# 411_Preliminary_Design__Group8_rev4_5.net
KiCad netlist of a schematic drawn in EAGLE
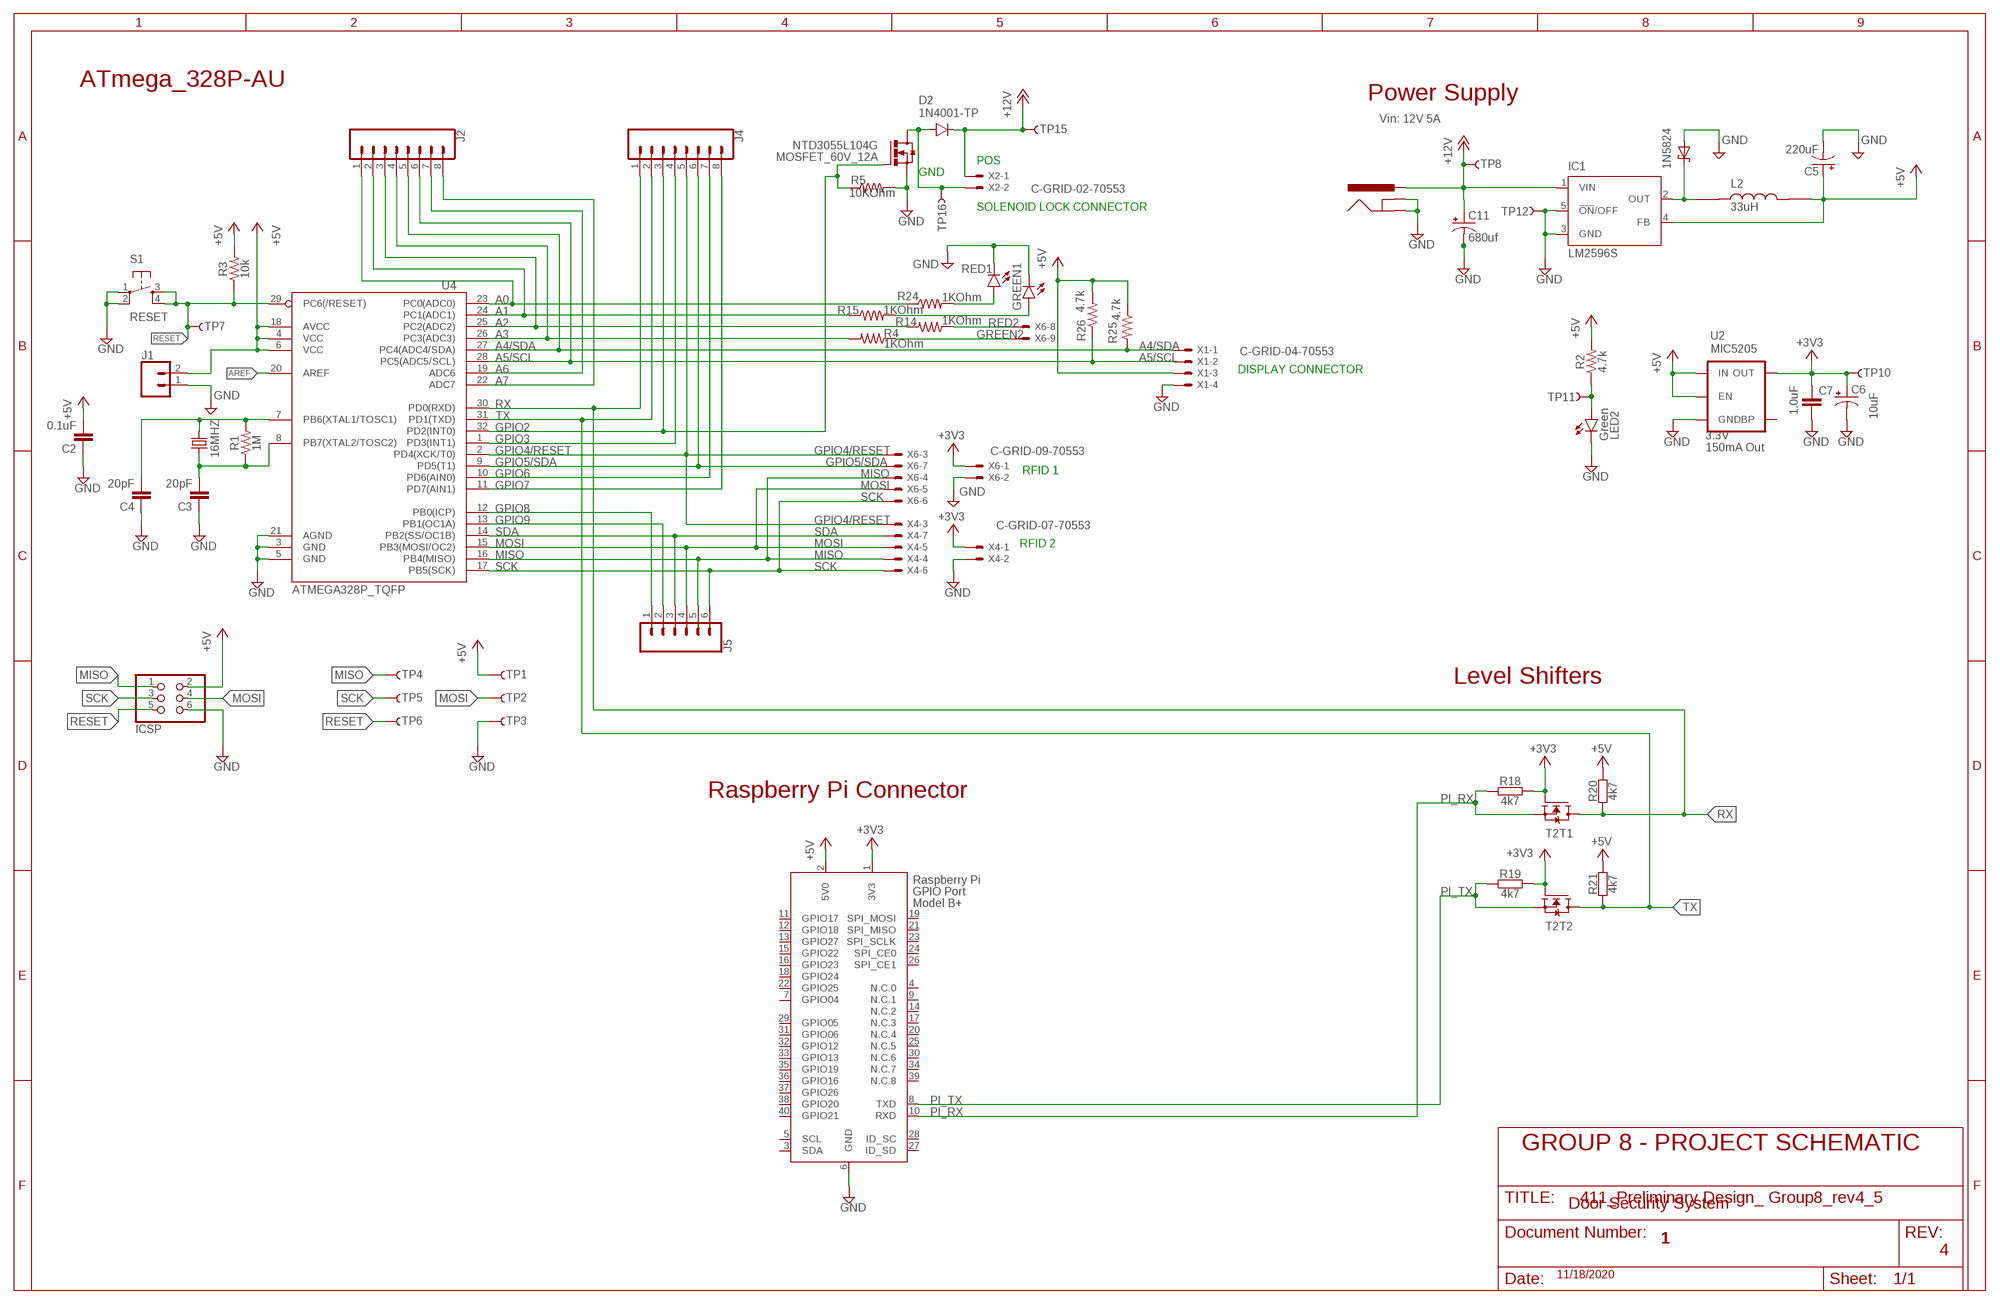
[diagram p0: schematic, sheet 1]

(export (version "E")
  (design (tool "Eeschema 10.0.6"))
  (components
    (comp (ref "1N5824")
      (value "SCHOTTKY-DIODECB429-15")
      (footprint "eagle-import:CB429-15")
      (libsource (lib "eagle-import") (part "SCHOTTKY-DIODECB429-15"))
    )
    (comp (ref "16MHZ")
      (value "16MHZ")
      (footprint "eagle-import:HC49_S")
      (libsource (lib "eagle-import") (part "CRYSTALHC49S"))
    )
    (comp (ref "C2")
      (value "0.1uF")
      (footprint "eagle-import:0603")
      (libsource (lib "eagle-import") (part "0.1UF-0603-25V-(+80/-20%)"))
    )
    (comp (ref "C3")
      (value "20pF")
      (footprint "eagle-import:0603")
      (libsource (lib "eagle-import") (part "0.1UF-0603-25V-(+80/-20%)"))
    )
    (comp (ref "C4")
      (value "20pF")
      (footprint "eagle-import:0603")
      (libsource (lib "eagle-import") (part "0.1UF-0603-25V-(+80/-20%)"))
    )
    (comp (ref "C5")
      (value "220uF")
      (footprint "eagle-import:153CLV-0605")
      (libsource (lib "eagle-import") (part "CPOL-US153CLV-0605"))
    )
    (comp (ref "C6")
      (value "10uF")
      (footprint "eagle-import:EIA3216")
      (libsource (lib "eagle-import") (part "10UF-POLAR-EIA3216-16V-10%(TANT)"))
    )
    (comp (ref "C7")
      (value "1.0uF")
      (footprint "eagle-import:0603")
      (libsource (lib "eagle-import") (part "1.0UF-0603-16V-10%"))
    )
    (comp (ref "C11")
      (value "680uf")
      (footprint "eagle-import:153CLV-0605")
      (libsource (lib "eagle-import") (part "CPOL-US153CLV-0605"))
    )
    (comp (ref "D2")
      (value "1N4001-TP")
      (footprint "eagle-import:DO41-10")
      (libsource (lib "eagle-import") (part "1N4004"))
    )
    (comp (ref "GREEN1")
      (value "LED5MM")
      (footprint "eagle-import:LED5MM")
      (libsource (lib "eagle-import") (part "led_259_LED5MM"))
    )
    (comp (ref "IC1")
      (value "LM2596S")
      (footprint "eagle-import:TO263-5")
      (fields (field (name "MF") "NATIONAL SEMICONDUCTOR") (field (name "MPN") "LM2596S-ADJ/NOPB"))
      (libsource (lib "eagle-import") (part "LM2596S"))
    )
    (comp (ref "ICSP")
      (value "ICSP")
      (footprint "eagle-import:2X03")
      (libsource (lib "eagle-import") (part "PINHD-2X3"))
    )
    (comp (ref "J1")
      (value "CONN_02")
      (footprint "eagle-import:1X02")
      (libsource (lib "eagle-import") (part "CONN_02"))
    )
    (comp (ref "J2")
      (value "CONN_08\"")
      (footprint "eagle-import:1X08")
      (libsource (lib "eagle-import") (part "CONN_08{dblquote}"))
    )
    (comp (ref "J3")
      (value "POWER_JACKSUPER_BOMB_DIGITY")
      (footprint "eagle-import:POWER_JACK_SMD_OVERPASTE_SUPER_BOMB_DIGITY")
      (libsource (lib "eagle-import") (part "POWER_JACKSUPER_BOMB_DIGITY"))
    )
    (comp (ref "J4")
      (value "CONN_08\"")
      (footprint "eagle-import:1X08")
      (libsource (lib "eagle-import") (part "CONN_08{dblquote}"))
    )
    (comp (ref "J5")
      (value "CONN_06SILK_FEMALE_PTH")
      (footprint "eagle-import:1X06")
      (libsource (lib "eagle-import") (part "CONN_06SILK_FEMALE_PTH"))
    )
    (comp (ref "L2")
      (value "33uH")
      (footprint "eagle-import:IND_#B953AS-330M=P3")
      (fields
        (field (name "DIGI-KEY_PART_NUMBER") "490-14099-1-ND")
        (field (name "MF") "Murata")
        (field (name "MP") "#B953AS-330M=P3")
      )
      (libsource (lib "eagle-import") (part "#B953AS-330M=P3"))
    )
    (comp (ref "LED2")
      (value "Green")
      (footprint "eagle-import:LED-1206")
      (libsource (lib "eagle-import") (part "LED1206"))
    )
    (comp (ref "MOSFET_60V_12A")
      (value "NTD3055L104G")
      (footprint "eagle-import:DPAK3")
      (fields (field (name "MANUFACTURER") "ON SEMICONDUCTORS") (field (name "CREATED_BY") "PCBLayout.com"))
      (libsource (lib "eagle-import") (part "NTD3055L104G"))
    )
    (comp (ref "R1")
      (value "1M")
      (footprint "eagle-import:0603")
      (libsource (lib "eagle-import") (part "10KOHM-0603-1/10W-1%"))
    )
    (comp (ref "R2")
      (value "4.7k")
      (footprint "eagle-import:0603")
      (libsource (lib "eagle-import") (part "4.7KOHM-0603-1/10W-1%"))
    )
    (comp (ref "R3")
      (value "10k")
      (footprint "eagle-import:0603")
      (libsource (lib "eagle-import") (part "10KOHM-0603-1/10W-1%"))
    )
    (comp (ref "R4")
      (value "1KOhm")
      (footprint "eagle-import:M1406")
      (libsource (lib "eagle-import") (part "R-US_M1406"))
    )
    (comp (ref "R5")
      (value "10KOhm")
      (footprint "eagle-import:M1406")
      (libsource (lib "eagle-import") (part "R-US_M1406"))
    )
    (comp (ref "R14")
      (value "1KOhm")
      (footprint "eagle-import:M1406")
      (libsource (lib "eagle-import") (part "R-US_M1406"))
    )
    (comp (ref "R15")
      (value "1KOhm")
      (footprint "eagle-import:M1406")
      (libsource (lib "eagle-import") (part "R-US_M1406"))
    )
    (comp (ref "R18")
      (value "4k7")
      (footprint "eagle-import:C0402")
      (libsource (lib "eagle-import") (part "RESISTOR-0402"))
    )
    (comp (ref "R19")
      (value "4k7")
      (footprint "eagle-import:C0402")
      (libsource (lib "eagle-import") (part "RESISTOR-0402"))
    )
    (comp (ref "R20")
      (value "4k7")
      (footprint "eagle-import:C0402")
      (libsource (lib "eagle-import") (part "RESISTOR-0402"))
    )
    (comp (ref "R21")
      (value "4k7")
      (footprint "eagle-import:C0402")
      (libsource (lib "eagle-import") (part "RESISTOR-0402"))
    )
    (comp (ref "R24")
      (value "1KOhm")
      (footprint "eagle-import:M1406")
      (libsource (lib "eagle-import") (part "R-US_M1406"))
    )
    (comp (ref "R25")
      (value "4.7k")
      (footprint "eagle-import:0603")
      (libsource (lib "eagle-import") (part "4.7KOHM-0603-1/10W-1%"))
    )
    (comp (ref "R26")
      (value "4.7k")
      (footprint "eagle-import:0603")
      (libsource (lib "eagle-import") (part "4.7KOHM-0603-1/10W-1%"))
    )
    (comp (ref "RED1")
      (value "LED5MM")
      (footprint "eagle-import:LED5MM")
      (fields (field (name "SPICEPREFIX") "L"))
      (libsource (lib "eagle-import") (part "led_259_LED5MM"))
    )
    (comp (ref "S1")
      (value "RESET")
      (footprint "eagle-import:TACTILE-SWITCH-SMD")
      (libsource (lib "eagle-import") (part "SWITCH_SPST_4_PINSQUARE"))
    )
    (comp (ref "T2")
      (value "BSS138PS")
      (footprint "eagle-import:SOT363")
      (libsource (lib "eagle-import") (part "BSS138PS"))
    )
    (comp (ref "TP1")
      (value "TP-3x5")
      (footprint "eagle-import:PAD.03X.05")
      (libsource (lib "eagle-import") (part "TEST-POINT3X5"))
    )
    (comp (ref "TP2")
      (value "TP-3x5")
      (footprint "eagle-import:PAD.03X.05")
      (libsource (lib "eagle-import") (part "TEST-POINT3X5"))
    )
    (comp (ref "TP3")
      (value "TP-3x5")
      (footprint "eagle-import:PAD.03X.05")
      (libsource (lib "eagle-import") (part "TEST-POINT3X5"))
    )
    (comp (ref "TP4")
      (value "TP-3x5")
      (footprint "eagle-import:PAD.03X.05")
      (libsource (lib "eagle-import") (part "TEST-POINT3X5"))
    )
    (comp (ref "TP5")
      (value "TP-3x5")
      (footprint "eagle-import:PAD.03X.05")
      (libsource (lib "eagle-import") (part "SparkFun-Passives_TEST-POINT3X5"))
    )
    (comp (ref "TP6")
      (value "TP-3x5")
      (footprint "eagle-import:PAD.03X.05")
      (libsource (lib "eagle-import") (part "TEST-POINT3X5"))
    )
    (comp (ref "TP7")
      (value "TP-3x5")
      (footprint "eagle-import:PAD.03X.05")
      (libsource (lib "eagle-import") (part "TEST-POINT3X5"))
    )
    (comp (ref "TP8")
      (value "TP-3x5")
      (footprint "eagle-import:PAD.03X.05")
      (libsource (lib "eagle-import") (part "TEST-POINT3X5"))
    )
    (comp (ref "TP10")
      (value "TP-3x5")
      (footprint "eagle-import:PAD.03X.05")
      (libsource (lib "eagle-import") (part "TEST-POINT3X5"))
    )
    (comp (ref "TP11")
      (value "TP-3x5")
      (footprint "eagle-import:PAD.03X.05")
      (libsource (lib "eagle-import") (part "TEST-POINT3X5"))
    )
    (comp (ref "TP12")
      (value "TP-3x5")
      (footprint "eagle-import:PAD.03X.05")
      (libsource (lib "eagle-import") (part "TEST-POINT3X5"))
    )
    (comp (ref "TP15")
      (value "TP-3x5")
      (footprint "eagle-import:PAD.03X.05")
      (libsource (lib "eagle-import") (part "TEST-POINT3X5"))
    )
    (comp (ref "TP16")
      (value "TP-3x5")
      (footprint "eagle-import:PAD.03X.05")
      (libsource (lib "eagle-import") (part "TEST-POINT3X5"))
    )
    (comp (ref "U2")
      (value "MIC5205")
      (footprint "eagle-import:SOT23-5")
      (libsource (lib "eagle-import") (part "MIC52053.3V"))
    )
    (comp (ref "U4")
      (value "ATMEGA328P_TQFP")
      (footprint "eagle-import:TQFP32-08")
      (libsource (lib "eagle-import") (part "ATMEGA328P_TQFP"))
    )
    (comp (ref "X1")
      (value "C-GRID-04-70553")
      (footprint "eagle-import:70553-04")
      (fields (field (name "MF") "MOLEX"))
      (libsource (lib "eagle-import") (part "C-GRID-04-70553"))
    )
    (comp (ref "X2")
      (value "C-GRID-02-70553")
      (footprint "eagle-import:70553-02")
      (fields (field (name "MF") "MOLEX"))
      (libsource (lib "eagle-import") (part "C-GRID-02-70553"))
    )
    (comp (ref "X4")
      (value "C-GRID-07-70553")
      (footprint "eagle-import:70553-07")
      (fields (field (name "MF") "MOLEX"))
      (libsource (lib "eagle-import") (part "C-GRID-07-70553"))
    )
    (comp (ref "X5")
      (value "RASPI_BOARD_B+_E4P")
      (footprint "eagle-import:RASPI_BOARD_B+_EDGES_4DRILL_PAD")
      (libsource (lib "eagle-import") (part "RASPI_BOARD_B+_E4P"))
    )
    (comp (ref "X6")
      (value "C-GRID-09-70553")
      (footprint "eagle-import:70553-09")
      (fields (field (name "MF") "MOLEX"))
      (libsource (lib "eagle-import") (part "C-GRID-09-70553"))
    )
  )
  (nets
    (net (code "1") (name "+3V3") (class "Default")
      (node (ref "C6") (pin "+") (pinfunction "+_+") (pintype "passive"))
      (node (ref "C7") (pin "1") (pinfunction "1_1") (pintype "passive"))
      (node (ref "R18") (pin "2") (pinfunction "2_2") (pintype "passive"))
      (node (ref "R19") (pin "2") (pinfunction "2_2") (pintype "passive"))
      (node (ref "T2") (pin "2") (pinfunction "G_2") (pintype "passive"))
      (node (ref "T2") (pin "5") (pinfunction "G_5") (pintype "passive"))
      (node (ref "TP10") (pin "P$1") (pinfunction "1_P$1") (pintype "bidirectional"))
      (node (ref "U2") (pin "5") (pinfunction "OUT_5") (pintype "passive"))
      (node (ref "X4") (pin "1") (pinfunction "S_1") (pintype "passive"))
      (node (ref "X5") (pin "1") (pinfunction "3V3_1") (pintype "power_in"))
      (node (ref "X6") (pin "1") (pinfunction "S_1") (pintype "passive"))
    )
    (net (code "2") (name "+5V") (class "Default")
      (node (ref "C2") (pin "2") (pinfunction "2_2") (pintype "passive"))
      (node (ref "C5") (pin "+") (pinfunction "+_+") (pintype "passive"))
      (node (ref "IC1") (pin "4") (pinfunction "FB_4") (pintype "input"))
      (node (ref "ICSP") (pin "2") (pinfunction "2_2") (pintype "passive"))
      (node (ref "J1") (pin "2") (pinfunction "2_2") (pintype "passive"))
      (node (ref "L2") (pin "2") (pinfunction "2_2") (pintype "passive"))
      (node (ref "R2") (pin "2") (pinfunction "2_2") (pintype "passive"))
      (node (ref "R20") (pin "2") (pinfunction "2_2") (pintype "passive"))
      (node (ref "R21") (pin "2") (pinfunction "2_2") (pintype "passive"))
      (node (ref "R25") (pin "1") (pinfunction "1_1") (pintype "passive"))
      (node (ref "R26") (pin "2") (pinfunction "2_2") (pintype "passive"))
      (node (ref "R3") (pin "2") (pinfunction "2_2") (pintype "passive"))
      (node (ref "TP1") (pin "P$1") (pinfunction "1_P$1") (pintype "bidirectional"))
      (node (ref "U2") (pin "1") (pinfunction "IN_1") (pintype "input"))
      (node (ref "U2") (pin "3") (pinfunction "EN_3") (pintype "input"))
      (node (ref "U4") (pin "18") (pinfunction "AVCC_18") (pintype "bidirectional"))
      (node (ref "U4") (pin "4") (pinfunction "VCC_4") (pintype "bidirectional"))
      (node (ref "U4") (pin "6") (pinfunction "VCC_6") (pintype "bidirectional"))
      (node (ref "X1") (pin "3") (pinfunction "S_3") (pintype "passive"))
      (node (ref "X5") (pin "2") (pinfunction "5V0_2") (pintype "power_in"))
    )
    (net (code "3") (name "+12V") (class "Default")
      (node (ref "C11") (pin "+") (pinfunction "+_+") (pintype "passive"))
      (node (ref "D2") (pin "C") (pinfunction "C_C") (pintype "passive"))
      (node (ref "IC1") (pin "1") (pinfunction "VIN_1") (pintype "input"))
      (node (ref "J3") (pin "VIN0") (pinfunction "PWR_VIN0") (pintype "bidirectional"))
      (node (ref "TP15") (pin "P$1") (pinfunction "1_P$1") (pintype "bidirectional"))
      (node (ref "TP8") (pin "P$1") (pinfunction "1_P$1") (pintype "bidirectional"))
      (node (ref "X2") (pin "1") (pinfunction "S_1") (pintype "passive"))
    )
    (net (code "4") (name "/A0") (class "Default")
      (node (ref "J2") (pin "1") (pinfunction "1_1") (pintype "passive"))
      (node (ref "R24") (pin "1") (pinfunction "1_1") (pintype "passive"))
      (node (ref "U4") (pin "23") (pinfunction "PC0(ADC0)_23") (pintype "bidirectional"))
    )
    (net (code "5") (name "/A1") (class "Default")
      (node (ref "J2") (pin "2") (pinfunction "2_2") (pintype "passive"))
      (node (ref "R15") (pin "1") (pinfunction "1_1") (pintype "passive"))
      (node (ref "U4") (pin "24") (pinfunction "PC1(ADC1)_24") (pintype "bidirectional"))
    )
    (net (code "6") (name "/A2") (class "Default")
      (node (ref "J2") (pin "3") (pinfunction "3_3") (pintype "passive"))
      (node (ref "R14") (pin "2") (pinfunction "2_2") (pintype "passive"))
      (node (ref "U4") (pin "25") (pinfunction "PC2(ADC2)_25") (pintype "bidirectional"))
    )
    (net (code "7") (name "/A3") (class "Default")
      (node (ref "J2") (pin "4") (pinfunction "4_4") (pintype "passive"))
      (node (ref "R4") (pin "2") (pinfunction "2_2") (pintype "passive"))
      (node (ref "U4") (pin "26") (pinfunction "PC3(ADC3)_26") (pintype "bidirectional"))
    )
    (net (code "8") (name "/A4{slash}SDA") (class "Default")
      (node (ref "J2") (pin "5") (pinfunction "5_5") (pintype "passive"))
      (node (ref "R25") (pin "2") (pinfunction "2_2") (pintype "passive"))
      (node (ref "U4") (pin "27") (pinfunction "PC4(ADC4/SDA)_27") (pintype "bidirectional"))
      (node (ref "X1") (pin "1") (pinfunction "S_1") (pintype "passive"))
    )
    (net (code "9") (name "/A5{slash}SCL") (class "Default")
      (node (ref "J2") (pin "6") (pinfunction "6_6") (pintype "passive"))
      (node (ref "R26") (pin "1") (pinfunction "1_1") (pintype "passive"))
      (node (ref "U4") (pin "28") (pinfunction "PC5(ADC5/SCL)_28") (pintype "bidirectional"))
      (node (ref "X1") (pin "2") (pinfunction "S_2") (pintype "passive"))
    )
    (net (code "10") (name "/A6") (class "Default")
      (node (ref "J2") (pin "7") (pinfunction "7_7") (pintype "passive"))
      (node (ref "U4") (pin "19") (pinfunction "ADC6_19") (pintype "bidirectional"))
    )
    (net (code "11") (name "/A7") (class "Default")
      (node (ref "J2") (pin "8") (pinfunction "8_8") (pintype "passive"))
      (node (ref "U4") (pin "22") (pinfunction "ADC7_22") (pintype "bidirectional"))
    )
    (net (code "12") (name "/GPIO2") (class "Default")
      (node (ref "J4") (pin "3") (pinfunction "3_3") (pintype "passive"))
      (node (ref "MOSFET_60V_12A") (pin "1") (pinfunction "G_1") (pintype "passive"))
      (node (ref "R5") (pin "1") (pinfunction "1_1") (pintype "passive"))
      (node (ref "U4") (pin "32") (pinfunction "PD2(INT0)_32") (pintype "bidirectional"))
    )
    (net (code "13") (name "/GPIO3") (class "Default")
      (node (ref "J4") (pin "4") (pinfunction "4_4") (pintype "passive"))
      (node (ref "U4") (pin "1") (pinfunction "PD3(INT1)_1") (pintype "bidirectional"))
    )
    (net (code "14") (name "/GPIO4{slash}RESET") (class "Default")
      (node (ref "J4") (pin "5") (pinfunction "5_5") (pintype "passive"))
      (node (ref "U4") (pin "2") (pinfunction "PD4(XCK/T0)_2") (pintype "bidirectional"))
      (node (ref "X4") (pin "3") (pinfunction "S_3") (pintype "passive"))
      (node (ref "X6") (pin "3") (pinfunction "S_3") (pintype "passive"))
    )
    (net (code "15") (name "/GPIO5{slash}SDA") (class "Default")
      (node (ref "J4") (pin "6") (pinfunction "6_6") (pintype "passive"))
      (node (ref "U4") (pin "9") (pinfunction "PD5(T1)_9") (pintype "bidirectional"))
      (node (ref "X6") (pin "7") (pinfunction "S_7") (pintype "passive"))
    )
    (net (code "16") (name "/GPIO6") (class "Default")
      (node (ref "J4") (pin "7") (pinfunction "7_7") (pintype "passive"))
      (node (ref "U4") (pin "10") (pinfunction "PD6(AIN0)_10") (pintype "bidirectional"))
    )
    (net (code "17") (name "/GPIO7") (class "Default")
      (node (ref "J4") (pin "8") (pinfunction "8_8") (pintype "passive"))
      (node (ref "U4") (pin "11") (pinfunction "PD7(AIN1)_11") (pintype "bidirectional"))
    )
    (net (code "18") (name "/GPIO8") (class "Default")
      (node (ref "J5") (pin "1") (pinfunction "1_1") (pintype "passive"))
      (node (ref "U4") (pin "12") (pinfunction "PB0(ICP)_12") (pintype "bidirectional"))
    )
    (net (code "19") (name "/GPIO9") (class "Default")
      (node (ref "J5") (pin "2") (pinfunction "2_2") (pintype "passive"))
      (node (ref "U4") (pin "13") (pinfunction "PB1(OC1A)_13") (pintype "bidirectional"))
    )
    (net (code "20") (name "/GREEN2") (class "Default")
      (node (ref "R4") (pin "1") (pinfunction "1_1") (pintype "passive"))
      (node (ref "X6") (pin "9") (pinfunction "S_9") (pintype "passive"))
    )
    (net (code "21") (name "/PI_RX") (class "Default")
      (node (ref "R18") (pin "1") (pinfunction "1_1") (pintype "passive"))
      (node (ref "T2") (pin "1") (pinfunction "S_1") (pintype "passive"))
      (node (ref "X5") (pin "10") (pinfunction "RXD_10") (pintype "bidirectional"))
    )
    (net (code "22") (name "/PI_TX") (class "Default")
      (node (ref "R19") (pin "1") (pinfunction "1_1") (pintype "passive"))
      (node (ref "T2") (pin "4") (pinfunction "S_4") (pintype "passive"))
      (node (ref "X5") (pin "8") (pinfunction "TXD_8") (pintype "bidirectional"))
    )
    (net (code "23") (name "/RED2") (class "Default")
      (node (ref "R14") (pin "1") (pinfunction "1_1") (pintype "passive"))
      (node (ref "X6") (pin "8") (pinfunction "S_8") (pintype "passive"))
    )
    (net (code "24") (name "/SDA") (class "Default")
      (node (ref "J5") (pin "3") (pinfunction "3_3") (pintype "passive"))
      (node (ref "U4") (pin "14") (pinfunction "PB2(SS/OC1B)_14") (pintype "bidirectional"))
      (node (ref "X4") (pin "7") (pinfunction "S_7") (pintype "passive"))
    )
    (net (code "25") (name "AREF") (class "Default")
      (node (ref "U4") (pin "20") (pinfunction "AREF_20") (pintype "bidirectional"))
    )
    (net (code "26") (name "GND") (class "Default")
      (node (ref "1N5824") (pin "A") (pinfunction "A_A") (pintype "passive"))
      (node (ref "C11") (pin "-") (pinfunction "-_-") (pintype "passive"))
      (node (ref "C2") (pin "1") (pinfunction "1_1") (pintype "passive"))
      (node (ref "C3") (pin "1") (pinfunction "1_1") (pintype "passive"))
      (node (ref "C4") (pin "1") (pinfunction "1_1") (pintype "passive"))
      (node (ref "C5") (pin "-") (pinfunction "-_-") (pintype "passive"))
      (node (ref "C6") (pin "-") (pinfunction "-_-") (pintype "passive"))
      (node (ref "C7") (pin "2") (pinfunction "2_2") (pintype "passive"))
      (node (ref "GREEN1") (pin "K") (pinfunction "C_K") (pintype "passive"))
      (node (ref "IC1") (pin "3") (pinfunction "GND_3") (pintype "power_in"))
      (node (ref "IC1") (pin "5") (pinfunction "~{ON}/OFF_5") (pintype "input"))
      (node (ref "ICSP") (pin "6") (pinfunction "6_6") (pintype "passive"))
      (node (ref "J1") (pin "1") (pinfunction "1_1") (pintype "passive"))
      (node (ref "J3") (pin "GND") (pinfunction "GNDBREAK_GND") (pintype "bidirectional"))
      (node (ref "J3") (pin "P$4") (pinfunction "GND_P$4") (pintype "bidirectional"))
      (node (ref "LED2") (pin "C") (pinfunction "C_C") (pintype "passive"))
      (node (ref "MOSFET_60V_12A") (pin "2") (pinfunction "S_2") (pintype "passive"))
      (node (ref "R5") (pin "2") (pinfunction "2_2") (pintype "passive"))
      (node (ref "RED1") (pin "K") (pinfunction "C_K") (pintype "passive"))
      (node (ref "S1") (pin "1") (pinfunction "1_1") (pintype "passive"))
      (node (ref "S1") (pin "2") (pinfunction "2_2") (pintype "passive"))
      (node (ref "TP12") (pin "P$1") (pinfunction "1_P$1") (pintype "bidirectional"))
      (node (ref "TP3") (pin "P$1") (pinfunction "1_P$1") (pintype "bidirectional"))
      (node (ref "U2") (pin "2") (pinfunction "GND_2") (pintype "input"))
      (node (ref "U4") (pin "21") (pinfunction "AGND_21") (pintype "bidirectional"))
      (node (ref "U4") (pin "3") (pinfunction "GND_3") (pintype "bidirectional"))
      (node (ref "U4") (pin "5") (pinfunction "GND_5") (pintype "bidirectional"))
      (node (ref "X1") (pin "4") (pinfunction "S_4") (pintype "passive"))
      (node (ref "X4") (pin "2") (pinfunction "S_2") (pintype "passive"))
      (node (ref "X5") (pin "6") (pinfunction "GND_6") (pintype "power_in"))
      (node (ref "X6") (pin "2") (pinfunction "S_2") (pintype "passive"))
    )
    (net (code "27") (name "MISO") (class "Default")
      (node (ref "ICSP") (pin "1") (pinfunction "1_1") (pintype "passive"))
      (node (ref "J5") (pin "5") (pinfunction "5_5") (pintype "passive"))
      (node (ref "TP4") (pin "P$1") (pinfunction "1_P$1") (pintype "bidirectional"))
      (node (ref "U4") (pin "16") (pinfunction "PB4(MISO)_16") (pintype "bidirectional"))
      (node (ref "X4") (pin "4") (pinfunction "S_4") (pintype "passive"))
      (node (ref "X6") (pin "4") (pinfunction "S_4") (pintype "passive"))
    )
    (net (code "28") (name "MOSI") (class "Default")
      (node (ref "ICSP") (pin "4") (pinfunction "4_4") (pintype "passive"))
      (node (ref "J5") (pin "4") (pinfunction "4_4") (pintype "passive"))
      (node (ref "TP2") (pin "P$1") (pinfunction "1_P$1") (pintype "bidirectional"))
      (node (ref "U4") (pin "15") (pinfunction "PB3(MOSI/OC2)_15") (pintype "bidirectional"))
      (node (ref "X4") (pin "5") (pinfunction "S_5") (pintype "passive"))
      (node (ref "X6") (pin "5") (pinfunction "S_5") (pintype "passive"))
    )
    (net (code "29") (name "Net-(GREEN1-PadA)") (class "Default")
      (node (ref "GREEN1") (pin "A") (pinfunction "A_A") (pintype "passive"))
      (node (ref "R15") (pin "2") (pinfunction "2_2") (pintype "passive"))
    )
    (net (code "30") (name "Net-(IC1-OUT)") (class "Default")
      (node (ref "1N5824") (pin "C") (pinfunction "C_C") (pintype "passive"))
      (node (ref "IC1") (pin "2") (pinfunction "OUT_2") (pintype "output"))
      (node (ref "L2") (pin "1") (pinfunction "1_1") (pintype "passive"))
    )
    (net (code "31") (name "Net-(MOSFET_60V_12A-D)") (class "Default")
      (node (ref "D2") (pin "A") (pinfunction "A_A") (pintype "passive"))
      (node (ref "MOSFET_60V_12A") (pin "3") (pinfunction "D_3") (pintype "passive"))
      (node (ref "TP16") (pin "P$1") (pinfunction "1_P$1") (pintype "bidirectional"))
      (node (ref "X2") (pin "2") (pinfunction "S_2") (pintype "passive"))
    )
    (net (code "32") (name "Net-(R24-Pad2)") (class "Default")
      (node (ref "R24") (pin "2") (pinfunction "2_2") (pintype "passive"))
      (node (ref "RED1") (pin "A") (pinfunction "A_A") (pintype "passive"))
    )
    (net (code "33") (name "Net-(TP11-1)") (class "Default")
      (node (ref "LED2") (pin "A") (pinfunction "A_A") (pintype "passive"))
      (node (ref "R2") (pin "1") (pinfunction "1_1") (pintype "passive"))
      (node (ref "TP11") (pin "P$1") (pinfunction "1_P$1") (pintype "bidirectional"))
    )
    (net (code "34") (name "Net-(U4-PB6(XTAL1{slash}TOSC1))") (class "Default")
      (node (ref "16MHZ") (pin "2") (pinfunction "2_2") (pintype "passive"))
      (node (ref "C4") (pin "2") (pinfunction "2_2") (pintype "passive"))
      (node (ref "R1") (pin "2") (pinfunction "2_2") (pintype "passive"))
      (node (ref "U4") (pin "7") (pinfunction "PB6(XTAL1/TOSC1)_7") (pintype "bidirectional"))
    )
    (net (code "35") (name "Net-(U4-PB7(XTAL2{slash}TOSC2))") (class "Default")
      (node (ref "16MHZ") (pin "1") (pinfunction "1_1") (pintype "passive"))
      (node (ref "C3") (pin "2") (pinfunction "2_2") (pintype "passive"))
      (node (ref "R1") (pin "1") (pinfunction "1_1") (pintype "passive"))
      (node (ref "U4") (pin "8") (pinfunction "PB7(XTAL2/TOSC2)_8") (pintype "bidirectional"))
    )
    (net (code "36") (name "RESET") (class "Default")
      (node (ref "ICSP") (pin "5") (pinfunction "5_5") (pintype "passive"))
      (node (ref "R3") (pin "1") (pinfunction "1_1") (pintype "passive"))
      (node (ref "S1") (pin "3") (pinfunction "3_3") (pintype "passive"))
      (node (ref "S1") (pin "4") (pinfunction "4_4") (pintype "passive"))
      (node (ref "TP6") (pin "P$1") (pinfunction "1_P$1") (pintype "bidirectional"))
      (node (ref "TP7") (pin "P$1") (pinfunction "1_P$1") (pintype "bidirectional"))
      (node (ref "U4") (pin "29") (pinfunction "PC6(/RESET)_29") (pintype "bidirectional"))
    )
    (net (code "37") (name "RX") (class "Default")
      (node (ref "J4") (pin "1") (pinfunction "1_1") (pintype "passive"))
      (node (ref "R20") (pin "1") (pinfunction "1_1") (pintype "passive"))
      (node (ref "T2") (pin "6") (pinfunction "D_6") (pintype "passive"))
      (node (ref "U4") (pin "30") (pinfunction "PD0(RXD)_30") (pintype "bidirectional"))
    )
    (net (code "38") (name "SCK") (class "Default")
      (node (ref "ICSP") (pin "3") (pinfunction "3_3") (pintype "passive"))
      (node (ref "J5") (pin "6") (pinfunction "6_6") (pintype "passive"))
      (node (ref "TP5") (pin "P$1") (pinfunction "1_P$1") (pintype "bidirectional"))
      (node (ref "U4") (pin "17") (pinfunction "PB5(SCK)_17") (pintype "bidirectional"))
      (node (ref "X4") (pin "6") (pinfunction "S_6") (pintype "passive"))
      (node (ref "X6") (pin "6") (pinfunction "S_6") (pintype "passive"))
    )
    (net (code "39") (name "TX") (class "Default")
      (node (ref "J4") (pin "2") (pinfunction "2_2") (pintype "passive"))
      (node (ref "R21") (pin "1") (pinfunction "1_1") (pintype "passive"))
      (node (ref "T2") (pin "3") (pinfunction "D_3") (pintype "passive"))
      (node (ref "U4") (pin "31") (pinfunction "PD1(TXD)_31") (pintype "bidirectional"))
    )
    (net (code "40") (name "unconnected-(U2-BP-Pad4)") (class "Default")
      (node (ref "U2") (pin "4") (pinfunction "BP_4") (pintype "input"))
    )
    (net (code "41") (name "unconnected-(X5-GPIO04-Pad7)") (class "Default")
      (node (ref "X5") (pin "7") (pinfunction "GPIO04_7") (pintype "bidirectional"))
    )
    (net (code "42") (name "unconnected-(X5-GPIO05-Pad29)") (class "Default")
      (node (ref "X5") (pin "29") (pinfunction "GPIO05_29") (pintype "no_connect"))
    )
    (net (code "43") (name "unconnected-(X5-GPIO06-Pad31)") (class "Default")
      (node (ref "X5") (pin "31") (pinfunction "GPIO06_31") (pintype "no_connect"))
    )
    (net (code "44") (name "unconnected-(X5-GPIO12-Pad32)") (class "Default")
      (node (ref "X5") (pin "32") (pinfunction "GPIO12_32") (pintype "no_connect"))
    )
    (net (code "45") (name "unconnected-(X5-GPIO13-Pad33)") (class "Default")
      (node (ref "X5") (pin "33") (pinfunction "GPIO13_33") (pintype "no_connect"))
    )
    (net (code "46") (name "unconnected-(X5-GPIO16-Pad36)") (class "Default")
      (node (ref "X5") (pin "36") (pinfunction "GPIO16_36") (pintype "no_connect"))
    )
    (net (code "47") (name "unconnected-(X5-GPIO17-Pad11)") (class "Default")
      (node (ref "X5") (pin "11") (pinfunction "GPIO17_11") (pintype "bidirectional"))
    )
    (net (code "48") (name "unconnected-(X5-GPIO18-Pad12)") (class "Default")
      (node (ref "X5") (pin "12") (pinfunction "GPIO18_12") (pintype "bidirectional"))
    )
    (net (code "49") (name "unconnected-(X5-GPIO19-Pad35)") (class "Default")
      (node (ref "X5") (pin "35") (pinfunction "GPIO19_35") (pintype "no_connect"))
    )
    (net (code "50") (name "unconnected-(X5-GPIO20-Pad38)") (class "Default")
      (node (ref "X5") (pin "38") (pinfunction "GPIO20_38") (pintype "no_connect"))
    )
    (net (code "51") (name "unconnected-(X5-GPIO21-Pad40)") (class "Default")
      (node (ref "X5") (pin "40") (pinfunction "GPIO21_40") (pintype "no_connect"))
    )
    (net (code "52") (name "unconnected-(X5-GPIO22-Pad15)") (class "Default")
      (node (ref "X5") (pin "15") (pinfunction "GPIO22_15") (pintype "bidirectional"))
    )
    (net (code "53") (name "unconnected-(X5-GPIO23-Pad16)") (class "Default")
      (node (ref "X5") (pin "16") (pinfunction "GPIO23_16") (pintype "bidirectional"))
    )
    (net (code "54") (name "unconnected-(X5-GPIO24-Pad18)") (class "Default")
      (node (ref "X5") (pin "18") (pinfunction "GPIO24_18") (pintype "bidirectional"))
    )
    (net (code "55") (name "unconnected-(X5-GPIO25-Pad22)") (class "Default")
      (node (ref "X5") (pin "22") (pinfunction "GPIO25_22") (pintype "bidirectional"))
    )
    (net (code "56") (name "unconnected-(X5-GPIO26-Pad37)") (class "Default")
      (node (ref "X5") (pin "37") (pinfunction "GPIO26_37") (pintype "no_connect"))
    )
    (net (code "57") (name "unconnected-(X5-GPIO27-Pad13)") (class "Default")
      (node (ref "X5") (pin "13") (pinfunction "GPIO27_13") (pintype "bidirectional"))
    )
    (net (code "58") (name "unconnected-(X5-ID_SC-Pad28)") (class "Default")
      (node (ref "X5") (pin "28") (pinfunction "ID_SC_28") (pintype "no_connect"))
    )
    (net (code "59") (name "unconnected-(X5-ID_SD-Pad27)") (class "Default")
      (node (ref "X5") (pin "27") (pinfunction "ID_SD_27") (pintype "no_connect"))
    )
    (net (code "60") (name "unconnected-(X5-N.C.0-Pad4)") (class "Default")
      (node (ref "X5") (pin "4") (pinfunction "N.C.0_4") (pintype "no_connect"))
    )
    (net (code "61") (name "unconnected-(X5-N.C.1-Pad9)") (class "Default")
      (node (ref "X5") (pin "9") (pinfunction "N.C.1_9") (pintype "no_connect"))
    )
    (net (code "62") (name "unconnected-(X5-N.C.2-Pad14)") (class "Default")
      (node (ref "X5") (pin "14") (pinfunction "N.C.2_14") (pintype "no_connect"))
    )
    (net (code "63") (name "unconnected-(X5-N.C.3-Pad17)") (class "Default")
      (node (ref "X5") (pin "17") (pinfunction "N.C.3_17") (pintype "no_connect"))
    )
    (net (code "64") (name "unconnected-(X5-N.C.4-Pad20)") (class "Default")
      (node (ref "X5") (pin "20") (pinfunction "N.C.4_20") (pintype "no_connect"))
    )
    (net (code "65") (name "unconnected-(X5-N.C.5-Pad25)") (class "Default")
      (node (ref "X5") (pin "25") (pinfunction "N.C.5_25") (pintype "no_connect"))
    )
    (net (code "66") (name "unconnected-(X5-N.C.6-Pad30)") (class "Default")
      (node (ref "X5") (pin "30") (pinfunction "N.C.6_30") (pintype "no_connect"))
    )
    (net (code "67") (name "unconnected-(X5-N.C.7-Pad34)") (class "Default")
      (node (ref "X5") (pin "34") (pinfunction "N.C.7_34") (pintype "no_connect"))
    )
    (net (code "68") (name "unconnected-(X5-N.C.8-Pad39)") (class "Default")
      (node (ref "X5") (pin "39") (pinfunction "N.C.8_39") (pintype "no_connect"))
    )
    (net (code "69") (name "unconnected-(X5-SCL-Pad5)") (class "Default")
      (node (ref "X5") (pin "5") (pinfunction "SCL_5") (pintype "bidirectional"))
    )
    (net (code "70") (name "unconnected-(X5-SDA-Pad3)") (class "Default")
      (node (ref "X5") (pin "3") (pinfunction "SDA_3") (pintype "bidirectional"))
    )
    (net (code "71") (name "unconnected-(X5-SPI_CE0-Pad24)") (class "Default")
      (node (ref "X5") (pin "24") (pinfunction "SPI_CE0_24") (pintype "bidirectional"))
    )
    (net (code "72") (name "unconnected-(X5-SPI_CE1-Pad26)") (class "Default")
      (node (ref "X5") (pin "26") (pinfunction "SPI_CE1_26") (pintype "bidirectional"))
    )
    (net (code "73") (name "unconnected-(X5-SPI_MISO-Pad21)") (class "Default")
      (node (ref "X5") (pin "21") (pinfunction "SPI_MISO_21") (pintype "bidirectional"))
    )
    (net (code "74") (name "unconnected-(X5-SPI_MOSI-Pad19)") (class "Default")
      (node (ref "X5") (pin "19") (pinfunction "SPI_MOSI_19") (pintype "bidirectional"))
    )
    (net (code "75") (name "unconnected-(X5-SPI_SCLK-Pad23)") (class "Default")
      (node (ref "X5") (pin "23") (pinfunction "SPI_SCLK_23") (pintype "bidirectional"))
    )
  )
)
